# design.net
KiCad netlist of a schematic drawn in EAGLE
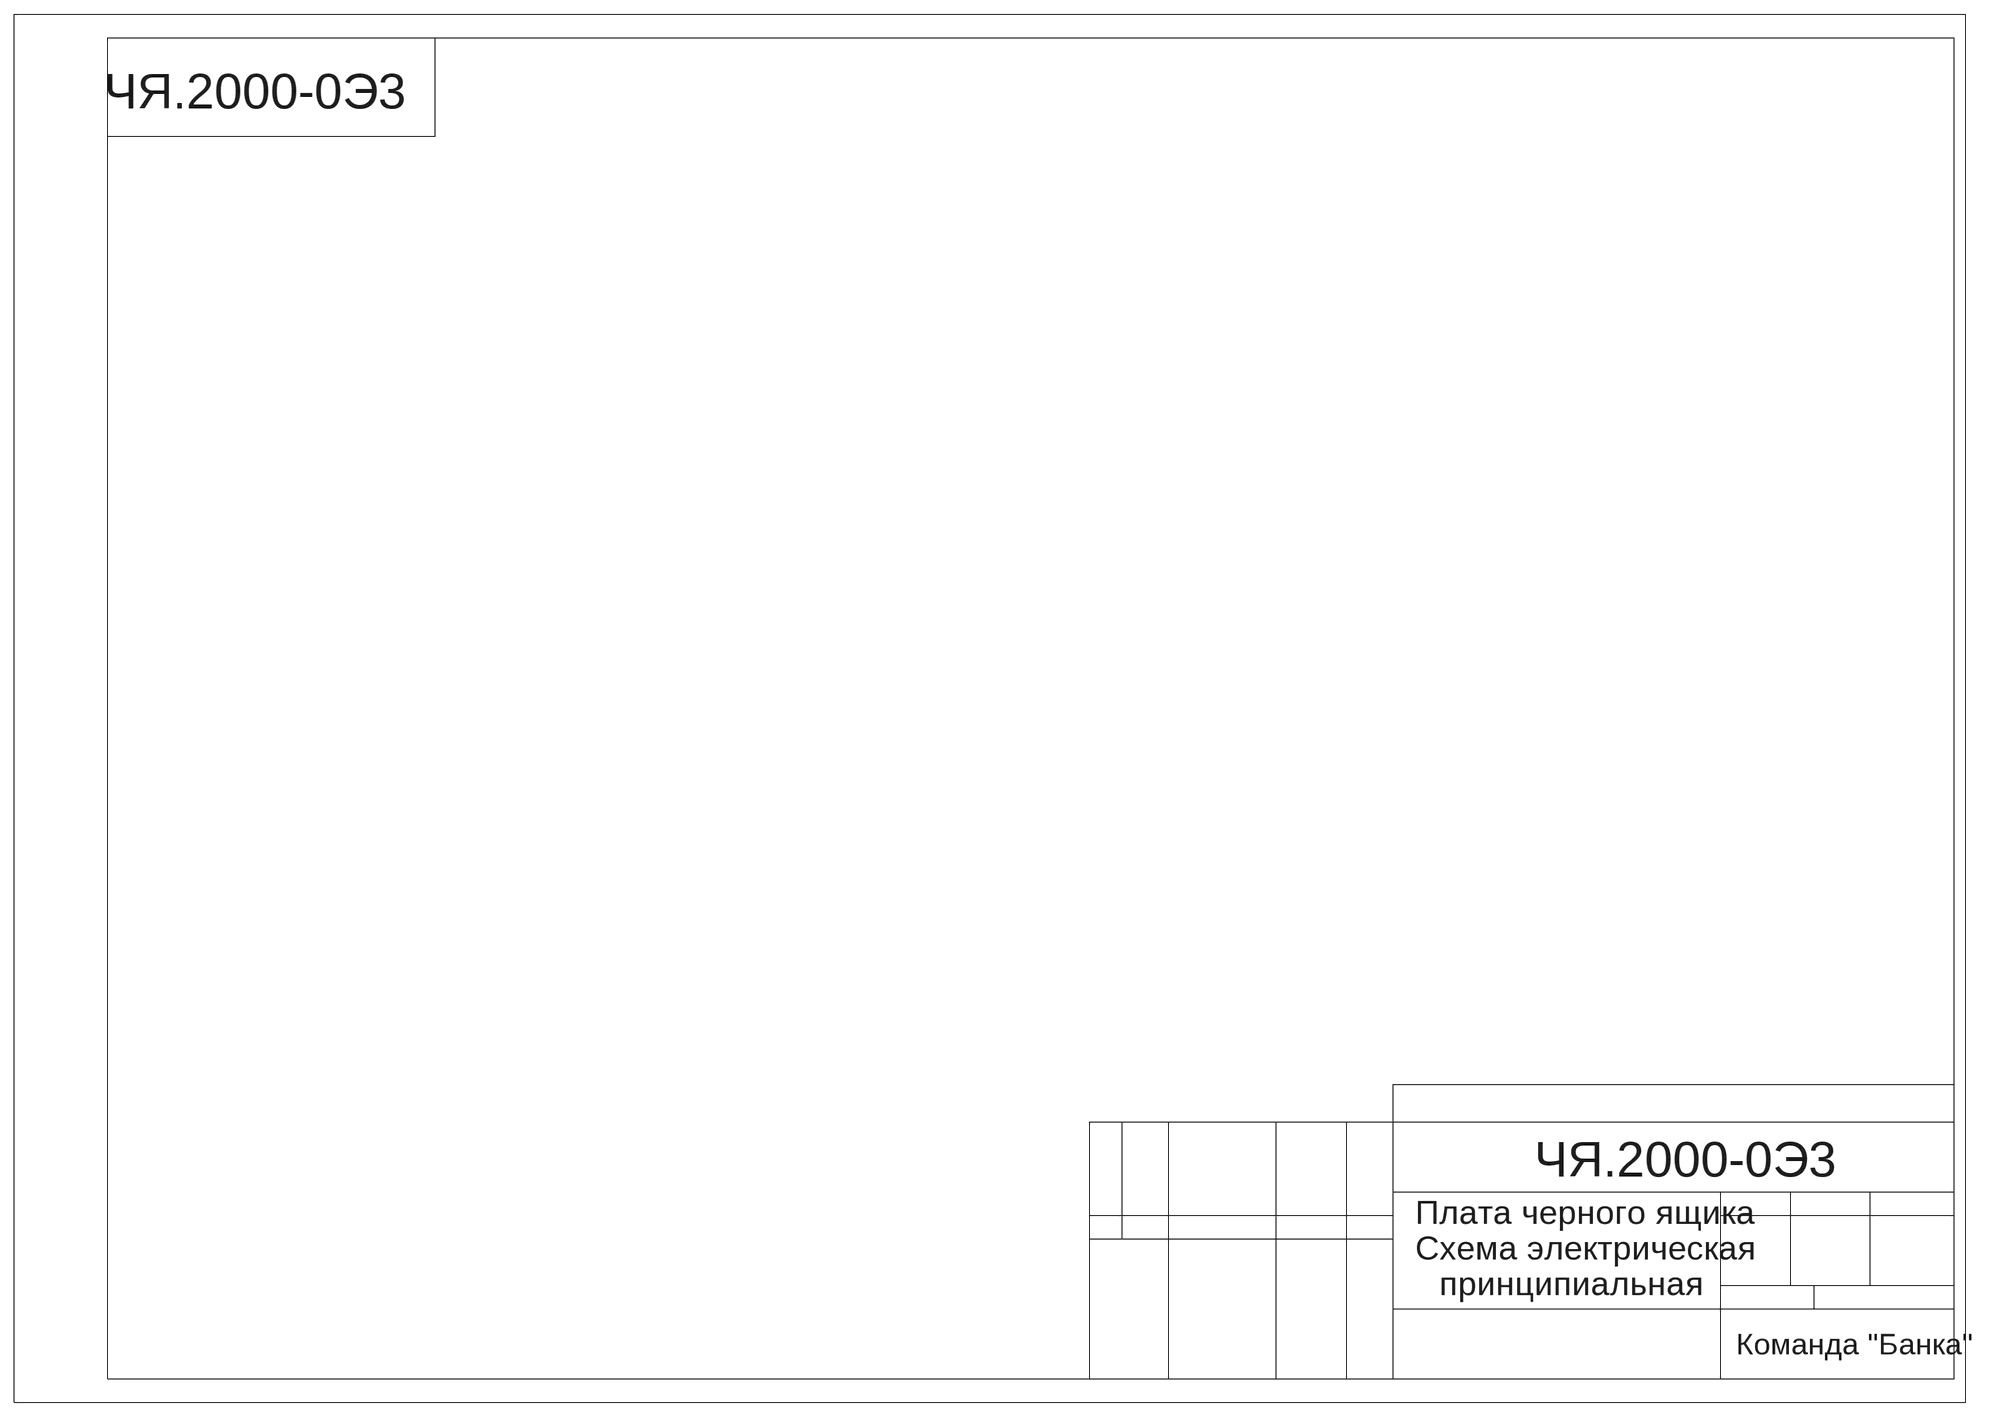
[diagram p0: schematic, sheet 1, part 1 of 2]
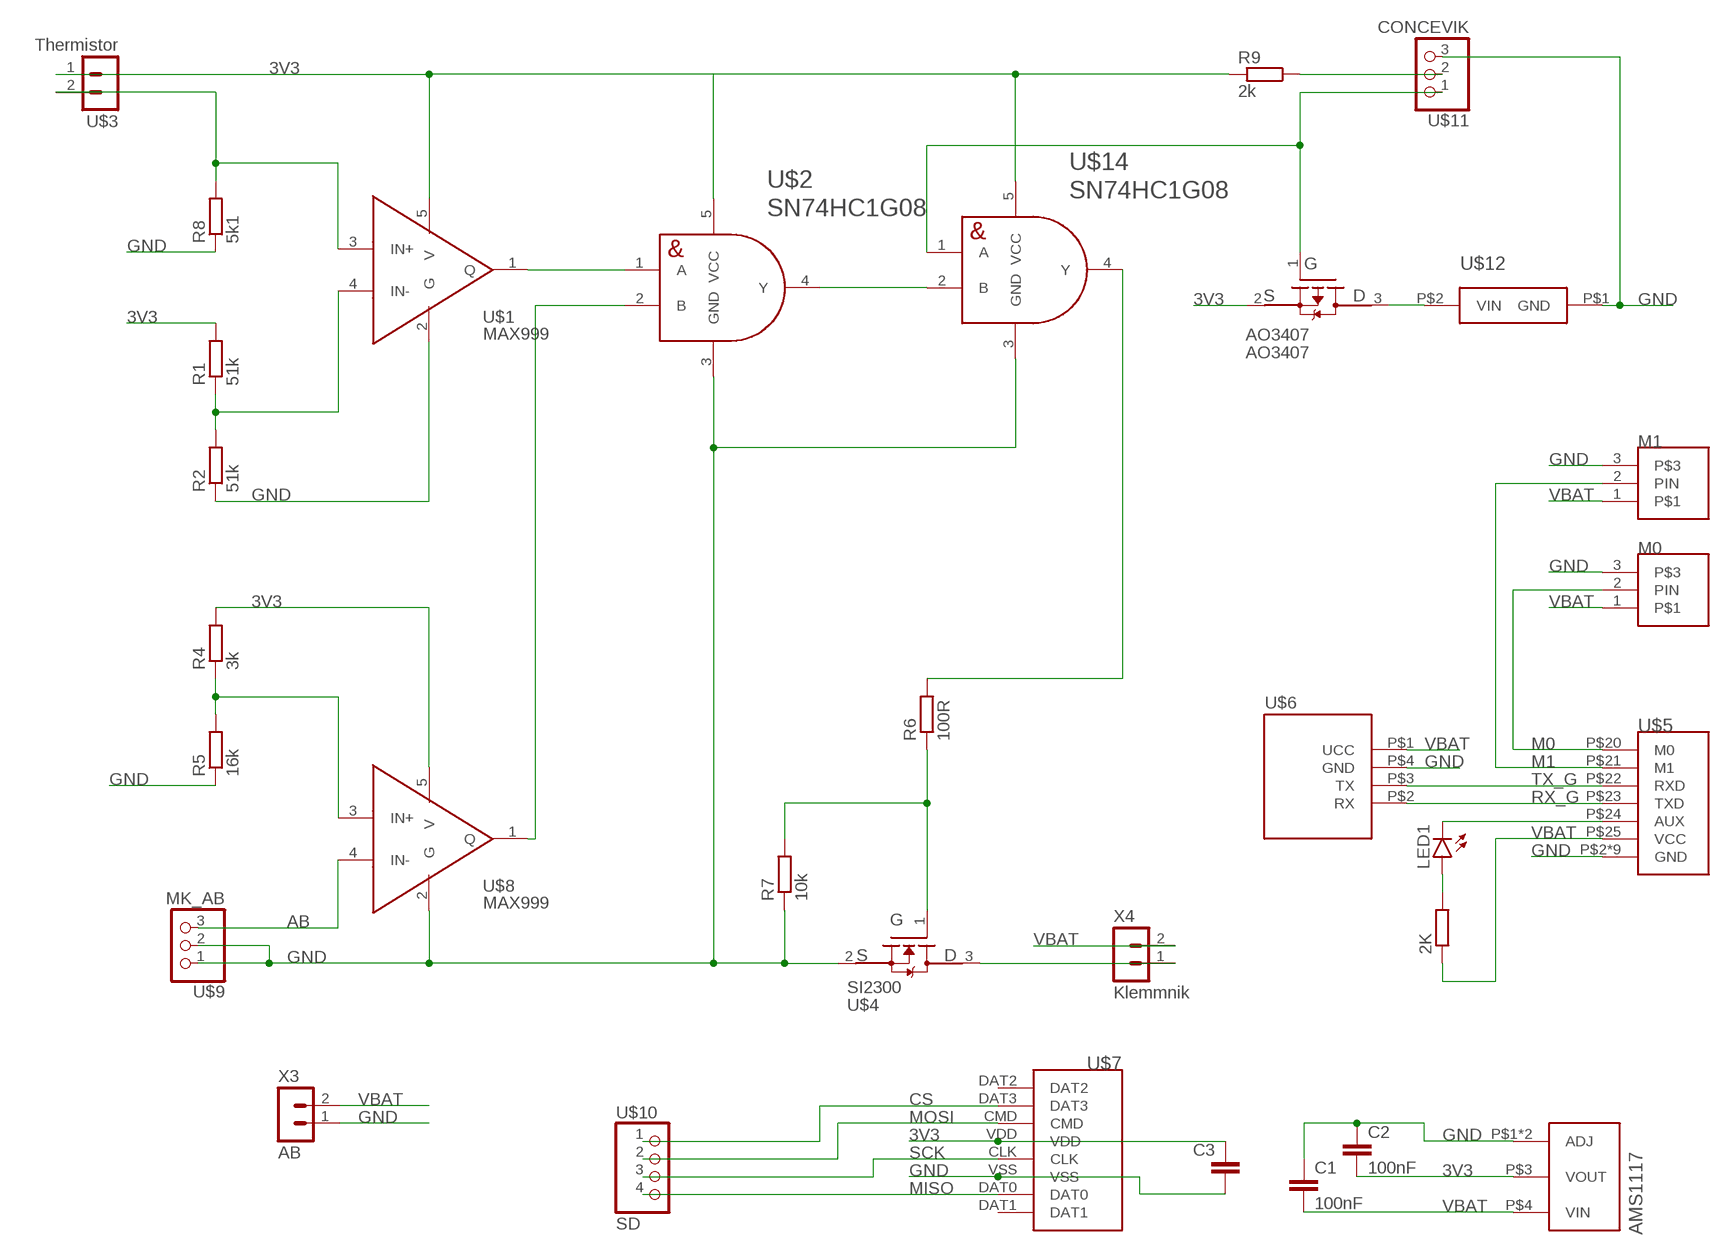
[diagram p1: schematic, sheet 1, part 2 of 2]

(export (version "E")
  (design (tool "Eeschema 10.0.6"))
  (components
    (comp (ref "2K")
      (value "R-EU_R0603")
      (footprint "eagle-import:R0603")
      (libsource (lib "eagle-import") (part "R-EU_R0603"))
    )
    (comp (ref "AMS1117")
      (value "AMS1117")
      (footprint "eagle-import:SOT223")
      (libsource (lib "eagle-import") (part "AMS1117"))
    )
    (comp (ref "AO3407")
      (value "AO3407")
      (footprint "eagle-import:SOT23-3")
      (libsource (lib "eagle-import") (part "AO3407"))
    )
    (comp (ref "C1")
      (value "100nF")
      (footprint "eagle-import:C0603")
      (libsource (lib "eagle-import") (part "C-EUC0603"))
    )
    (comp (ref "C2")
      (value "100nF")
      (footprint "eagle-import:C0603")
      (libsource (lib "eagle-import") (part "C-EUC0603"))
    )
    (comp (ref "C3")
      (value "C-EUC0603")
      (footprint "eagle-import:C0603")
      (libsource (lib "eagle-import") (part "C-EUC0603"))
    )
    (comp (ref "LED1")
      (value "LEDCHIP-LED0603")
      (footprint "eagle-import:CHIP-LED0603")
      (libsource (lib "eagle-import") (part "LEDCHIP-LED0603"))
    )
    (comp (ref "M0")
      (value "CONNECT_3")
      (footprint "eagle-import:CONNECT_3")
      (libsource (lib "eagle-import") (part "CONNECT_3"))
    )
    (comp (ref "M1")
      (value "CONNECT_3")
      (footprint "eagle-import:CONNECT_3")
      (libsource (lib "eagle-import") (part "CONNECT_3"))
    )
    (comp (ref "R1")
      (value "51k")
      (footprint "eagle-import:R0603")
      (libsource (lib "eagle-import") (part "R-EU_R0603"))
    )
    (comp (ref "R2")
      (value "51k")
      (footprint "eagle-import:R0603")
      (libsource (lib "eagle-import") (part "R-EU_R0603"))
    )
    (comp (ref "R4")
      (value "3k")
      (footprint "eagle-import:R0603")
      (libsource (lib "eagle-import") (part "R-EU_R0603"))
    )
    (comp (ref "R5")
      (value "16k")
      (footprint "eagle-import:R0603")
      (libsource (lib "eagle-import") (part "R-EU_R0603"))
    )
    (comp (ref "R6")
      (value "100R")
      (footprint "eagle-import:R0603")
      (libsource (lib "eagle-import") (part "R-EU_R0603"))
    )
    (comp (ref "R7")
      (value "10k")
      (footprint "eagle-import:R0603")
      (libsource (lib "eagle-import") (part "R-EU_R0603"))
    )
    (comp (ref "R8")
      (value "5k1")
      (footprint "eagle-import:R0603")
      (libsource (lib "eagle-import") (part "R-EU_R0603"))
    )
    (comp (ref "R9")
      (value "2k")
      (footprint "eagle-import:R0603")
      (libsource (lib "eagle-import") (part "R-EU_R0603"))
    )
    (comp (ref "U$1")
      (value "MAX999")
      (footprint "eagle-import:SOT23-5")
      (libsource (lib "eagle-import") (part "MAX999"))
    )
    (comp (ref "U$2")
      (value "SN74HC1G08")
      (footprint "eagle-import:SOT23-5")
      (libsource (lib "eagle-import") (part "SN74HC1G08"))
    )
    (comp (ref "U$3")
      (value "Thermistor")
      (footprint "eagle-import:53047-02")
      (libsource (lib "eagle-import") (part "MOLEX-2-1.25"))
    )
    (comp (ref "U$4")
      (value "SI2300")
      (footprint "eagle-import:SOT23-3")
      (libsource (lib "eagle-import") (part "SI2300"))
    )
    (comp (ref "U$5")
      (value "E220-400T22S")
      (footprint "eagle-import:E220-400T22S")
      (libsource (lib "eagle-import") (part "E220-400T22S"))
    )
    (comp (ref "U$6")
      (value "GPS-NEO7M")
      (footprint "eagle-import:GPS-NEO7M")
      (libsource (lib "eagle-import") (part "GPS-NEO7M"))
    )
    (comp (ref "U$7") (value "SD") (footprint "eagle-import:SD") (libsource (lib "eagle-import") (part "SD")))
    (comp (ref "U$8")
      (value "MAX999")
      (footprint "eagle-import:SOT23-5")
      (libsource (lib "eagle-import") (part "MAX999"))
    )
    (comp (ref "U$9")
      (value "MK_AB")
      (footprint "eagle-import:53047-03")
      (libsource (lib "eagle-import") (part "MOLEX-3-1.25"))
    )
    (comp (ref "U$10")
      (value "SD")
      (footprint "eagle-import:53047-04")
      (libsource (lib "eagle-import") (part "MOLEX-4-1.25"))
    )
    (comp (ref "U$11")
      (value "CONCEVIK")
      (footprint "eagle-import:53047-03")
      (libsource (lib "eagle-import") (part "MOLEX-3-1.25"))
    )
    (comp (ref "U$12")
      (value "BUZZERS8R6")
      (footprint "eagle-import:BUZZER-S8R12")
      (libsource (lib "eagle-import") (part "BUZZERS8R6"))
    )
    (comp (ref "U$14")
      (value "SN74HC1G08")
      (footprint "eagle-import:SOT23-5")
      (libsource (lib "eagle-import") (part "SN74HC1G08"))
    )
    (comp (ref "X3")
      (value "AB")
      (footprint "eagle-import:JST-2-2.5")
      (libsource (lib "eagle-import") (part "JST-2-2.5"))
    )
    (comp (ref "X4")
      (value "Klemmnik")
      (footprint "eagle-import:JST-2-2.5")
      (libsource (lib "eagle-import") (part "JST-2-2.5"))
    )
  )
  (nets
    (net (code "1") (name "/3V3") (class "Default")
      (node (ref "AMS1117") (pin "P$3") (pinfunction "VOUT_P$3") (pintype "bidirectional"))
      (node (ref "AO3407") (pin "2") (pinfunction "PS_2") (pintype "passive"))
      (node (ref "C2") (pin "2") (pinfunction "2_2") (pintype "passive"))
      (node (ref "C3") (pin "1") (pinfunction "1_1") (pintype "passive"))
      (node (ref "R1") (pin "2") (pinfunction "2_2") (pintype "passive"))
      (node (ref "R4") (pin "2") (pinfunction "2_2") (pintype "passive"))
      (node (ref "R9") (pin "2") (pinfunction "2_2") (pintype "passive"))
      (node (ref "U$1") (pin "5") (pinfunction "V_5") (pintype "bidirectional"))
      (node (ref "U$14") (pin "5") (pinfunction "VCC_5") (pintype "bidirectional"))
      (node (ref "U$2") (pin "5") (pinfunction "VCC_5") (pintype "bidirectional"))
      (node (ref "U$3") (pin "1") (pinfunction "1_1") (pintype "passive"))
      (node (ref "U$7") (pin "VDD") (pinfunction "VDD_VDD") (pintype "bidirectional"))
      (node (ref "U$8") (pin "5") (pinfunction "V_5") (pintype "bidirectional"))
    )
    (net (code "2") (name "/AB") (class "Default")
      (node (ref "U$8") (pin "4") (pinfunction "IN-_4") (pintype "bidirectional"))
      (node (ref "U$9") (pin "3") (pinfunction "3_3") (pintype "passive"))
    )
    (net (code "3") (name "/CS") (class "Default")
      (node (ref "U$10") (pin "1") (pinfunction "1_1") (pintype "passive"))
      (node (ref "U$7") (pin "DAT3") (pinfunction "DAT3_DAT3") (pintype "bidirectional"))
    )
    (net (code "4") (name "/GND") (class "Default")
      (node (ref "AMS1117") (pin "P$1") (pinfunction "ADJ_P$1") (pintype "bidirectional"))
      (node (ref "AMS1117") (pin "P$2") (pinfunction "ADJ_P$2") (pintype "bidirectional"))
      (node (ref "C1") (pin "1") (pinfunction "1_1") (pintype "passive"))
      (node (ref "C2") (pin "1") (pinfunction "1_1") (pintype "passive"))
      (node (ref "C3") (pin "2") (pinfunction "2_2") (pintype "passive"))
      (node (ref "M0") (pin "3") (pinfunction "P$3_3") (pintype "bidirectional"))
      (node (ref "M1") (pin "3") (pinfunction "P$3_3") (pintype "bidirectional"))
      (node (ref "R2") (pin "1") (pinfunction "1_1") (pintype "passive"))
      (node (ref "R5") (pin "1") (pinfunction "1_1") (pintype "passive"))
      (node (ref "R7") (pin "1") (pinfunction "1_1") (pintype "passive"))
      (node (ref "R8") (pin "1") (pinfunction "1_1") (pintype "passive"))
      (node (ref "U$1") (pin "2") (pinfunction "G_2") (pintype "bidirectional"))
      (node (ref "U$11") (pin "3") (pinfunction "3_3") (pintype "passive"))
      (node (ref "U$12") (pin "P$1") (pinfunction "GND_P$1") (pintype "bidirectional"))
      (node (ref "U$14") (pin "3") (pinfunction "GND_3") (pintype "bidirectional"))
      (node (ref "U$2") (pin "3") (pinfunction "GND_3") (pintype "bidirectional"))
      (node (ref "U$4") (pin "2") (pinfunction "NS_2") (pintype "passive"))
      (node (ref "U$5") (pin "P$11") (pinfunction "GND_P$11") (pintype "bidirectional"))
      (node (ref "U$5") (pin "P$13") (pinfunction "GND_P$13") (pintype "bidirectional"))
      (node (ref "U$5") (pin "P$14") (pinfunction "GND_P$14") (pintype "bidirectional"))
      (node (ref "U$5") (pin "P$15") (pinfunction "GND_P$15") (pintype "bidirectional"))
      (node (ref "U$5") (pin "P$16") (pinfunction "GND_P$16") (pintype "bidirectional"))
      (node (ref "U$5") (pin "P$19") (pinfunction "GND_P$19") (pintype "bidirectional"))
      (node (ref "U$5") (pin "P$2") (pinfunction "GND_P$2") (pintype "bidirectional"))
      (node (ref "U$5") (pin "P$26") (pinfunction "GND_P$26") (pintype "bidirectional"))
      (node (ref "U$5") (pin "P$8") (pinfunction "GND_P$8") (pintype "bidirectional"))
      (node (ref "U$6") (pin "P$4") (pinfunction "GND_P$4") (pintype "bidirectional"))
      (node (ref "U$7") (pin "VSS") (pinfunction "VSS_VSS") (pintype "bidirectional"))
      (node (ref "U$8") (pin "2") (pinfunction "G_2") (pintype "bidirectional"))
      (node (ref "U$9") (pin "1") (pinfunction "1_1") (pintype "passive"))
      (node (ref "U$9") (pin "2") (pinfunction "2_2") (pintype "passive"))
      (node (ref "X3") (pin "1") (pinfunction "1_1") (pintype "passive"))
    )
    (net (code "5") (name "/M0") (class "Default")
      (node (ref "M0") (pin "2") (pinfunction "PIN_2") (pintype "bidirectional"))
      (node (ref "U$5") (pin "P$20") (pinfunction "M0_P$20") (pintype "bidirectional"))
    )
    (net (code "6") (name "/M1") (class "Default")
      (node (ref "M1") (pin "2") (pinfunction "PIN_2") (pintype "bidirectional"))
      (node (ref "U$5") (pin "P$21") (pinfunction "M1_P$21") (pintype "bidirectional"))
    )
    (net (code "7") (name "/MISO") (class "Default")
      (node (ref "U$10") (pin "4") (pinfunction "4_4") (pintype "passive"))
      (node (ref "U$7") (pin "DAT0") (pinfunction "DAT0_DAT0") (pintype "bidirectional"))
    )
    (net (code "8") (name "/MOSI") (class "Default")
      (node (ref "U$10") (pin "2") (pinfunction "2_2") (pintype "passive"))
      (node (ref "U$7") (pin "CMD") (pinfunction "CMD_CMD") (pintype "bidirectional"))
    )
    (net (code "9") (name "/RX_G") (class "Default")
      (node (ref "U$5") (pin "P$23") (pinfunction "TXD_P$23") (pintype "bidirectional"))
      (node (ref "U$6") (pin "P$2") (pinfunction "RX_P$2") (pintype "bidirectional"))
    )
    (net (code "10") (name "/SCK") (class "Default")
      (node (ref "U$10") (pin "3") (pinfunction "3_3") (pintype "passive"))
      (node (ref "U$7") (pin "CLK") (pinfunction "CLK_CLK") (pintype "bidirectional"))
    )
    (net (code "11") (name "/TX_G") (class "Default")
      (node (ref "U$5") (pin "P$22") (pinfunction "RXD_P$22") (pintype "bidirectional"))
      (node (ref "U$6") (pin "P$3") (pinfunction "TX_P$3") (pintype "bidirectional"))
    )
    (net (code "12") (name "/VBAT") (class "Default")
      (node (ref "2K") (pin "1") (pinfunction "1_1") (pintype "passive"))
      (node (ref "AMS1117") (pin "P$4") (pinfunction "VIN_P$4") (pintype "bidirectional"))
      (node (ref "C1") (pin "2") (pinfunction "2_2") (pintype "passive"))
      (node (ref "M0") (pin "1") (pinfunction "P$1_1") (pintype "bidirectional"))
      (node (ref "M1") (pin "1") (pinfunction "P$1_1") (pintype "bidirectional"))
      (node (ref "U$5") (pin "P$25") (pinfunction "VCC_P$25") (pintype "bidirectional"))
      (node (ref "U$6") (pin "P$1") (pinfunction "UCC_P$1") (pintype "bidirectional"))
      (node (ref "X3") (pin "2") (pinfunction "2_2") (pintype "passive"))
      (node (ref "X4") (pin "2") (pinfunction "2_2") (pintype "passive"))
    )
    (net (code "13") (name "Net-(2K-Pad2)") (class "Default")
      (node (ref "2K") (pin "2") (pinfunction "2_2") (pintype "passive"))
      (node (ref "LED1") (pin "A") (pinfunction "A_A") (pintype "passive"))
    )
    (net (code "14") (name "Net-(AO3407-PD)") (class "Default")
      (node (ref "AO3407") (pin "3") (pinfunction "PD_3") (pintype "passive"))
      (node (ref "U$12") (pin "P$2") (pinfunction "VIN_P$2") (pintype "bidirectional"))
    )
    (net (code "15") (name "Net-(AO3407-PG)") (class "Default")
      (node (ref "AO3407") (pin "1") (pinfunction "PG_1") (pintype "passive"))
      (node (ref "U$11") (pin "1") (pinfunction "1_1") (pintype "passive"))
      (node (ref "U$14") (pin "1") (pinfunction "A_1") (pintype "bidirectional"))
    )
    (net (code "16") (name "Net-(R9-Pad1)") (class "Default")
      (node (ref "R9") (pin "1") (pinfunction "1_1") (pintype "passive"))
      (node (ref "U$11") (pin "2") (pinfunction "2_2") (pintype "passive"))
    )
    (net (code "17") (name "Net-(U$1-IN+)") (class "Default")
      (node (ref "R8") (pin "2") (pinfunction "2_2") (pintype "passive"))
      (node (ref "U$1") (pin "3") (pinfunction "IN+_3") (pintype "bidirectional"))
      (node (ref "U$3") (pin "2") (pinfunction "2_2") (pintype "passive"))
    )
    (net (code "18") (name "Net-(U$1-IN-)") (class "Default")
      (node (ref "R1") (pin "1") (pinfunction "1_1") (pintype "passive"))
      (node (ref "R2") (pin "2") (pinfunction "2_2") (pintype "passive"))
      (node (ref "U$1") (pin "4") (pinfunction "IN-_4") (pintype "bidirectional"))
    )
    (net (code "19") (name "Net-(U$1-Q)") (class "Default")
      (node (ref "U$1") (pin "1") (pinfunction "Q_1") (pintype "bidirectional"))
      (node (ref "U$2") (pin "1") (pinfunction "A_1") (pintype "bidirectional"))
    )
    (net (code "20") (name "Net-(U$2-B)") (class "Default")
      (node (ref "U$2") (pin "2") (pinfunction "B_2") (pintype "bidirectional"))
      (node (ref "U$8") (pin "1") (pinfunction "Q_1") (pintype "bidirectional"))
    )
    (net (code "21") (name "Net-(U$4-ND)") (class "Default")
      (node (ref "U$4") (pin "3") (pinfunction "ND_3") (pintype "passive"))
      (node (ref "X4") (pin "1") (pinfunction "1_1") (pintype "passive"))
    )
    (net (code "22") (name "Net-(U$4-NG)") (class "Default")
      (node (ref "R6") (pin "1") (pinfunction "1_1") (pintype "passive"))
      (node (ref "R7") (pin "2") (pinfunction "2_2") (pintype "passive"))
      (node (ref "U$4") (pin "1") (pinfunction "NG_1") (pintype "passive"))
    )
    (net (code "23") (name "Net-(U$5-AUX)") (class "Default")
      (node (ref "LED1") (pin "C") (pinfunction "C_C") (pintype "passive"))
      (node (ref "U$5") (pin "P$24") (pinfunction "AUX_P$24") (pintype "bidirectional"))
    )
    (net (code "24") (name "Net-(U$8-IN+)") (class "Default")
      (node (ref "R4") (pin "1") (pinfunction "1_1") (pintype "passive"))
      (node (ref "R5") (pin "2") (pinfunction "2_2") (pintype "passive"))
      (node (ref "U$8") (pin "3") (pinfunction "IN+_3") (pintype "bidirectional"))
    )
    (net (code "25") (name "Net-(U$14-B)") (class "Default")
      (node (ref "U$14") (pin "2") (pinfunction "B_2") (pintype "bidirectional"))
      (node (ref "U$2") (pin "4") (pinfunction "Y_4") (pintype "bidirectional"))
    )
    (net (code "26") (name "Net-(U$14-Y)") (class "Default")
      (node (ref "R6") (pin "2") (pinfunction "2_2") (pintype "passive"))
      (node (ref "U$14") (pin "4") (pinfunction "Y_4") (pintype "bidirectional"))
    )
    (net (code "27") (name "unconnected-(U$7-PadDAT1)") (class "Default")
      (node (ref "U$7") (pin "DAT1") (pinfunction "DAT1_DAT1") (pintype "bidirectional"))
    )
    (net (code "28") (name "unconnected-(U$7-PadDAT2)") (class "Default")
      (node (ref "U$7") (pin "DAT2") (pinfunction "DAT2_DAT2") (pintype "bidirectional"))
    )
  )
)
